# TPS2663.net
KiCad netlist of a schematic drawn in Altium Designer
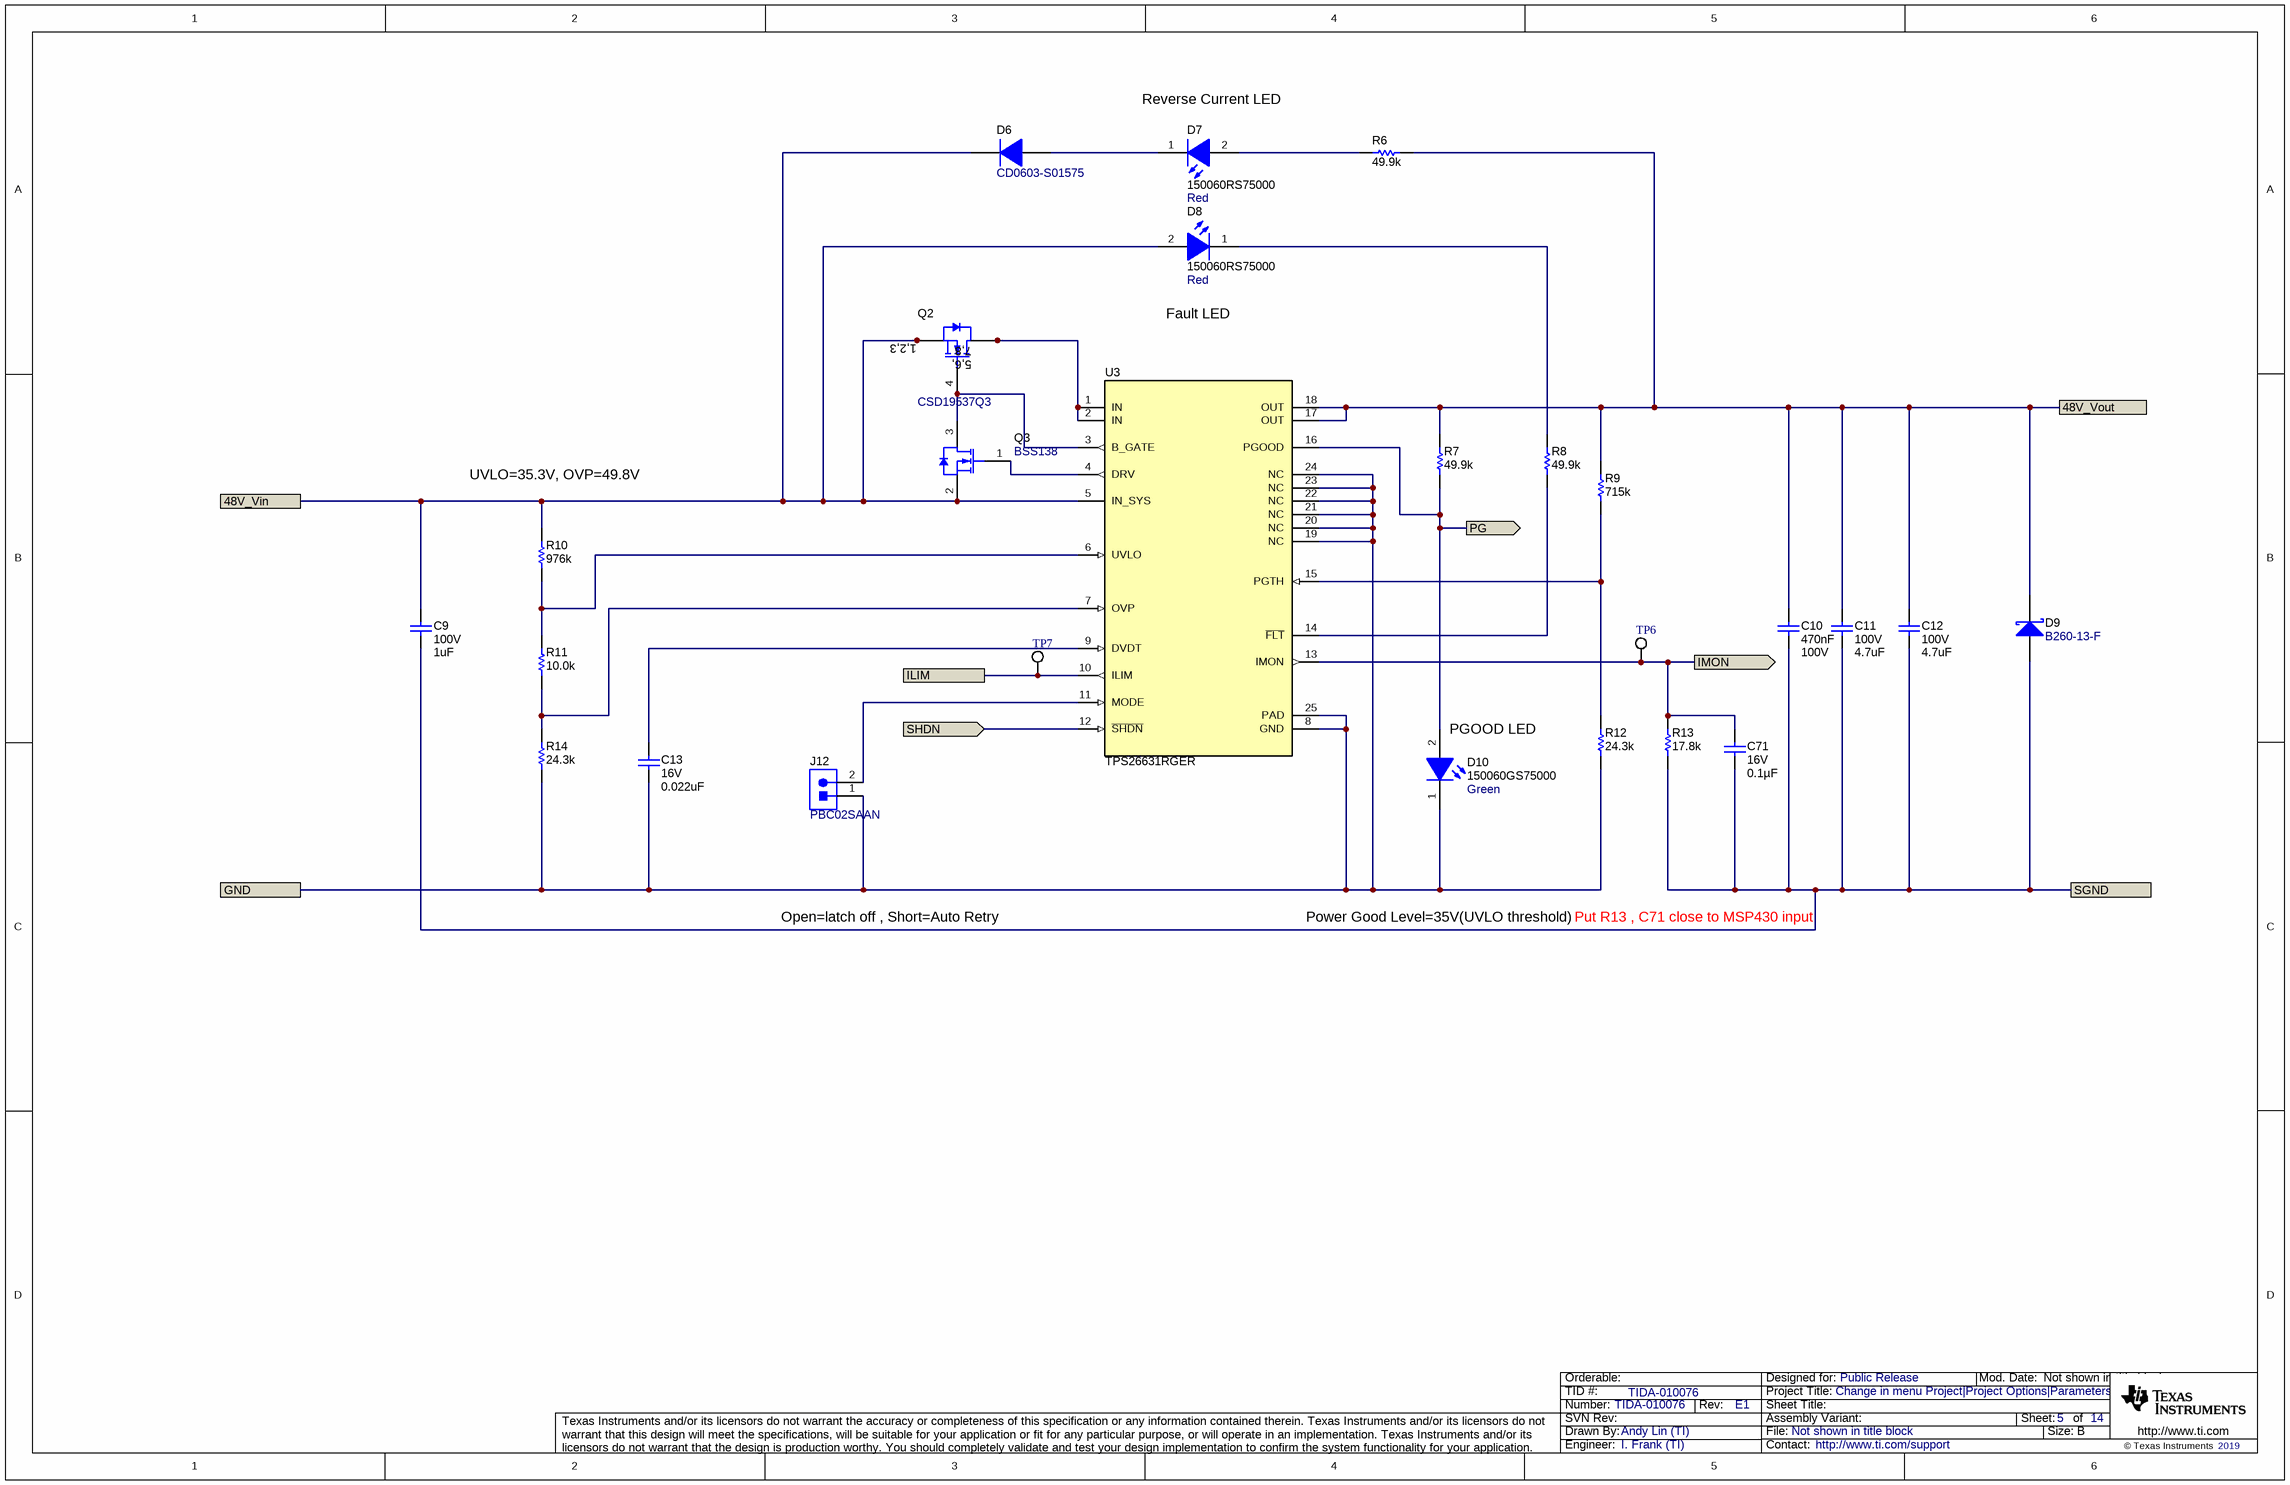
[diagram p0: TPS2663.SchDoc]

(export (version "E")
  (design (tool "Eeschema 10.0.6"))
  (components
    (comp (ref "C9")
      (value "GRM31CR72A105KA01L")
      (footprint "1206_180")
      (description "CAP, CERM, 1 uF, 100 V, +/- 10%, X7R, 1206")
      (fields
        (field (name "MANUFACTURER") "MuRata")
        (field (name "VDC_V") "100V")
        (field (name "VALUEDISPLAYED") "1uF")
        (field (name "PUBLISHER") "Texas Instruments")
      )
      (libsource (lib "Altium Vault - TI") (part "Capacitor"))
    )
    (comp (ref "C10")
      (value "GRM21BR72A474KA73L")
      (footprint "0805_HV")
      (description "CAP, CERM, 0.47 uF, 100 V, +/- 10%, X7R, 0805")
      (fields
        (field (name "MANUFACTURER") "MuRata")
        (field (name "CAP_F") "470nF")
        (field (name "VDC_V") "100V")
        (field (name "PUBLISHER") "Texas Instruments")
      )
      (libsource (lib "Altium Vault - TI") (part "Capacitor"))
    )
    (comp (ref "C11")
      (value "GRM32DC72A475KE01L")
      (footprint "1210_220")
      (description "CAP, CERM, 4.7 uF, 100 V, +/- 10%, X7S, 1210")
      (fields
        (field (name "MANUFACTURER") "MuRata")
        (field (name "VDC_V") "100V")
        (field (name "VALUEDISPLAYED") "4.7uF")
        (field (name "PUBLISHER") "Texas Instruments")
      )
      (libsource (lib "Altium Vault - TI") (part "Capacitor"))
    )
    (comp (ref "C12")
      (value "GRM32DC72A475KE01L")
      (footprint "1210_220")
      (description "CAP, CERM, 4.7 uF, 100 V, +/- 10%, X7S, 1210")
      (fields
        (field (name "MANUFACTURER") "MuRata")
        (field (name "VDC_V") "100V")
        (field (name "VALUEDISPLAYED") "4.7uF")
        (field (name "PUBLISHER") "Texas Instruments")
      )
      (libsource (lib "Altium Vault - TI") (part "Capacitor"))
    )
    (comp (ref "C13")
      (value "GRM155R71C223KA01D")
      (footprint "0402")
      (description "CAP, CERM, 0.022 uF, 16 V, +/- 10%, X7R, 0402")
      (fields
        (field (name "MANUFACTURER") "MuRata")
        (field (name "VDC_V") "16V")
        (field (name "VALUEDISPLAYED") "0.022uF")
        (field (name "PUBLISHER") "Texas Instruments")
      )
      (libsource (lib "Altium Vault - TI") (part "Capacitor"))
    )
    (comp (ref "C71")
      (value "GCM155R71C104JA55D")
      (footprint "0402")
      (description "CAP, CERM, 0.1 µF, 16 V,+/- 5%, X7R, AEC-Q200 Grade 1, 0402")
      (fields
        (field (name "MANUFACTURER") "MuRata")
        (field (name "VDC_V") "16V")
        (field (name "VALUEDISPLAYED") "0.1µF")
      )
      (libsource (lib "Altium Vault - TI") (part "Capacitor"))
    )
    (comp (ref "D6")
      (value "CD0603-S01575")
      (footprint "Diode_0603")
      (description "Diode, Switching, 100 V, 0.15 A, 0603 Diode")
      (fields (field (name "MANUFACTURER") "Bourns"))
      (libsource (lib "Altium Vault - TI") (part "DIODE"))
    )
    (comp (ref "D7")
      (value "150060RS75000")
      (footprint "WL-SMCW_RED")
      (description "LED, Red, SMD")
      (fields (field (name "ALTIUM_VALUE") "Red") (field (name "MANUFACTURER") "Wurth Elektronik"))
      (libsource (lib "Altium Vault - TI") (part "LED_A2_K1"))
    )
    (comp (ref "D8")
      (value "150060RS75000")
      (footprint "WL-SMCW_RED")
      (description "LED, Red, SMD")
      (fields (field (name "ALTIUM_VALUE") "Red") (field (name "MANUFACTURER") "Wurth Elektronik"))
      (libsource (lib "Altium Vault - TI") (part "LED_A2_K1"))
    )
    (comp (ref "D9")
      (value "B260-13-F")
      (footprint "SMB")
      (description "Diode, Schottky, 60 V, 2 A, SMB")
      (fields (field (name "MANUFACTURER") "Diodes Inc."))
      (libsource (lib "Altium Vault - TI") (part "DIODE_SCHOTTKY"))
    )
    (comp (ref "D10")
      (value "150060GS75000")
      (footprint "WL-SMCW_GREEN")
      (description "LED, Green, SMD")
      (fields (field (name "ALTIUM_VALUE") "Green") (field (name "MANUFACTURER") "Wurth Elektronik"))
      (libsource (lib "Altium Vault - TI") (part "LED_A2_K1"))
    )
    (comp (ref "J12")
      (value "PBC02SAAN")
      (footprint "Sullins_PBC02SAAN")
      (description "Header, 100mil, 2x1, Gold, TH")
      (fields
        (field (name "MANUFACTURER") "Sullins Connector Solutions")
        (field (name "PUBLISHER") "Texas Instruments")
      )
      (libsource (lib "Altium Vault - TI") (part "Header_2x1"))
    )
    (comp (ref "Q2")
      (value "CSD19537Q3")
      (footprint "DQG0008A")
      (description "MOSFET, N-CH, 100 V, 50 A, DQG0008A (VSON-CLIP-8)")
      (fields
        (field (name "MANUFACTURER") "Texas Instruments")
        (field (name "PUBLISHER") "Texas Instruments")
      )
      (libsource (lib "Altium Vault - TI") (part "MOSFET_N_D56789G4S123"))
    )
    (comp (ref "Q3")
      (value "BSS138")
      (footprint "SOT-23")
      (description "MOSFET, N-CH, 50 V, 0.22 A, SOT-23")
      (fields
        (field (name "MANUFACTURER") "Fairchild Semiconductor")
        (field (name "PUBLISHER") "Texas Instruments")
      )
      (libsource (lib "Altium Vault - TI") (part "MOSFET_N_D3G1S2"))
    )
    (comp (ref "R6")
      (value "CRCW060349K9FKEA")
      (footprint "0603")
      (description "RES, 49.9 k, 1%, 0.1 W, 0603")
      (fields
        (field (name "MANUFACTURER") "Vishay-Dale")
        (field (name "VALUEDISPLAYED") "49.9k")
        (field (name "PUBLISHER") "Texas Instruments")
      )
      (libsource (lib "Altium Vault - TI") (part "Resistor"))
    )
    (comp (ref "R7")
      (value "CRCW060349K9FKEA")
      (footprint "0603")
      (description "RES, 49.9 k, 1%, 0.1 W, 0603")
      (fields
        (field (name "MANUFACTURER") "Vishay-Dale")
        (field (name "VALUEDISPLAYED") "49.9k")
        (field (name "PUBLISHER") "Texas Instruments")
      )
      (libsource (lib "Altium Vault - TI") (part "Resistor"))
    )
    (comp (ref "R8")
      (value "CRCW060349K9FKEA")
      (footprint "0603")
      (description "RES, 49.9 k, 1%, 0.1 W, 0603")
      (fields
        (field (name "MANUFACTURER") "Vishay-Dale")
        (field (name "VALUEDISPLAYED") "49.9k")
        (field (name "PUBLISHER") "Texas Instruments")
      )
      (libsource (lib "Altium Vault - TI") (part "Resistor"))
    )
    (comp (ref "R9")
      (value "CRCW0402715KFKED")
      (footprint "0402")
      (description "RES, 715 k, 1%, 0.063 W, AEC-Q200 Grade 0, 0402")
      (fields (field (name "MANUFACTURER") "Vishay-Dale") (field (name "VALUEDISPLAYED") "715k"))
      (libsource (lib "Altium Vault - TI") (part "Resistor"))
    )
    (comp (ref "R10")
      (value "CRCW0402976KFKED")
      (footprint "0402")
      (description "RES, 976 k, 1%, 0.063 W, AEC-Q200 Grade 0, 0402")
      (fields (field (name "MANUFACTURER") "Vishay-Dale") (field (name "VALUEDISPLAYED") "976k"))
      (libsource (lib "Altium Vault - TI") (part "Resistor"))
    )
    (comp (ref "R11")
      (value "CRCW040210K0FKED")
      (footprint "0402")
      (description "RES, 10.0 k, 1%, 0.063 W, AEC-Q200 Grade 0, 0402")
      (fields (field (name "MANUFACTURER") "Vishay-Dale") (field (name "VALUEDISPLAYED") "10.0k"))
      (libsource (lib "Altium Vault - TI") (part "Resistor"))
    )
    (comp (ref "R12")
      (value "CRCW040224K3FKED")
      (footprint "0402")
      (description "RES, 24.3 k, 1%, 0.063 W, AEC-Q200 Grade 0, 0402")
      (fields (field (name "MANUFACTURER") "Vishay-Dale") (field (name "VALUEDISPLAYED") "24.3k"))
      (libsource (lib "Altium Vault - TI") (part "Resistor"))
    )
    (comp (ref "R13")
      (value "CRCW040217K8FKED")
      (footprint "0402")
      (description "RES, 17.8 k, 1%, 0.063 W, AEC-Q200 Grade 0, 0402")
      (fields (field (name "MANUFACTURER") "Vishay-Dale") (field (name "VALUEDISPLAYED") "17.8k"))
      (libsource (lib "Altium Vault - TI") (part "Resistor"))
    )
    (comp (ref "R14")
      (value "CRCW040224K3FKED")
      (footprint "0402")
      (description "RES, 24.3 k, 1%, 0.063 W, AEC-Q200 Grade 0, 0402")
      (fields (field (name "MANUFACTURER") "Vishay-Dale") (field (name "VALUEDISPLAYED") "24.3k"))
      (libsource (lib "Altium Vault - TI") (part "Resistor"))
    )
    (comp (ref "TP6")
      (value "5002")
      (footprint "Keystone5002")
      (description "Test Point, Miniature, White, TH")
      (fields (field (name "MANUFACTURER") "Keystone") (field (name "PUBLISHER") "Texas Instruments"))
      (libsource (lib "Altium Vault - TI") (part "5002"))
    )
    (comp (ref "TP7")
      (value "5002")
      (footprint "Keystone5002")
      (description "Test Point, Miniature, White, TH")
      (fields (field (name "MANUFACTURER") "Keystone") (field (name "PUBLISHER") "Texas Instruments"))
      (libsource (lib "Altium Vault - TI") (part "5002"))
    )
    (comp (ref "U3")
      (value "TPS26631RGER")
      (footprint "RGE0024H")
      (description "4.5V - 60V, 6A 29mΩ eFuse with Reverse Polarity Protection, RGE0024H (VQFN-24)")
      (fields
        (field (name "PARTNUMBER") "TPS26631RGER")
        (field (name "ALTERNATE PARTNUMBER") "TPS26631RGET")
        (field (name "MANUFACTURER") "Texas Instruments")
      )
      (libsource (lib "Altium Vault - TI") (part "TPS26630_1"))
    )
  )
  (nets
    (net (code "1") (name "/48V_Vin") (class "Default")
      (node (ref "C9") (pin "1") (pinfunction "1_1") (pintype "passive"))
      (node (ref "D6") (pin "1") (pinfunction "K_1") (pintype "passive"))
      (node (ref "D8") (pin "2") (pinfunction "A_2") (pintype "passive"))
      (node (ref "Q2") (pin "1") (pinfunction "S_1") (pintype "passive"))
      (node (ref "Q2") (pin "2") (pinfunction "S_2") (pintype "passive"))
      (node (ref "Q2") (pin "3") (pinfunction "S_3") (pintype "passive"))
      (node (ref "Q3") (pin "2") (pinfunction "S_2") (pintype "passive"))
      (node (ref "R10") (pin "2") (pinfunction "2_2") (pintype "passive"))
      (node (ref "U3") (pin "5") (pinfunction "IN_SYS_5") (pintype "power_in"))
    )
    (net (code "2") (name "/48V_Vout") (class "Default")
      (node (ref "C10") (pin "1") (pinfunction "1_1") (pintype "passive"))
      (node (ref "C11") (pin "1") (pinfunction "1_1") (pintype "passive"))
      (node (ref "C12") (pin "1") (pinfunction "1_1") (pintype "passive"))
      (node (ref "D9") (pin "1") (pinfunction "K_1") (pintype "passive"))
      (node (ref "R6") (pin "1") (pinfunction "1_1") (pintype "passive"))
      (node (ref "R7") (pin "2") (pinfunction "2_2") (pintype "passive"))
      (node (ref "R9") (pin "2") (pinfunction "2_2") (pintype "passive"))
      (node (ref "U3") (pin "17") (pinfunction "OUT_17") (pintype "power_in"))
      (node (ref "U3") (pin "18") (pinfunction "OUT_18") (pintype "power_in"))
    )
    (net (code "3") (name "/GND") (class "Default")
      (node (ref "C13") (pin "2") (pinfunction "2_2") (pintype "passive"))
      (node (ref "D10") (pin "1") (pinfunction "K_1") (pintype "passive"))
      (node (ref "J12") (pin "1") (pinfunction "1_1") (pintype "passive"))
      (node (ref "R12") (pin "1") (pinfunction "1_1") (pintype "passive"))
      (node (ref "R14") (pin "1") (pinfunction "1_1") (pintype "passive"))
      (node (ref "U3") (pin "19") (pinfunction "NC_19") (pintype "passive"))
      (node (ref "U3") (pin "20") (pinfunction "NC_20") (pintype "passive"))
      (node (ref "U3") (pin "21") (pinfunction "NC_21") (pintype "passive"))
      (node (ref "U3") (pin "22") (pinfunction "NC_22") (pintype "passive"))
      (node (ref "U3") (pin "23") (pinfunction "NC_23") (pintype "passive"))
      (node (ref "U3") (pin "24") (pinfunction "NC_24") (pintype "passive"))
      (node (ref "U3") (pin "25") (pinfunction "PAD_25") (pintype "power_in"))
      (node (ref "U3") (pin "8") (pinfunction "GND_8") (pintype "power_in"))
    )
    (net (code "4") (name "/ILIM") (class "Default")
      (node (ref "TP7") (pin "1") (pintype "passive"))
      (node (ref "U3") (pin "10") (pinfunction "ILIM_10") (pintype "output"))
    )
    (net (code "5") (name "/IMON") (class "Default")
      (node (ref "C71") (pin "1") (pinfunction "1_1") (pintype "passive"))
      (node (ref "R13") (pin "2") (pinfunction "2_2") (pintype "passive"))
      (node (ref "TP6") (pin "1") (pintype "passive"))
      (node (ref "U3") (pin "13") (pinfunction "IMON_13") (pintype "output"))
    )
    (net (code "6") (name "/PG") (class "Default")
      (node (ref "D10") (pin "2") (pinfunction "A_2") (pintype "passive"))
      (node (ref "R7") (pin "1") (pinfunction "1_1") (pintype "passive"))
      (node (ref "U3") (pin "16") (pinfunction "PGOOD_16") (pintype "open_collector"))
    )
    (net (code "7") (name "/SGND") (class "Default")
      (node (ref "C10") (pin "2") (pinfunction "2_2") (pintype "passive"))
      (node (ref "C11") (pin "2") (pinfunction "2_2") (pintype "passive"))
      (node (ref "C12") (pin "2") (pinfunction "2_2") (pintype "passive"))
      (node (ref "C71") (pin "2") (pinfunction "2_2") (pintype "passive"))
      (node (ref "C9") (pin "2") (pinfunction "2_2") (pintype "passive"))
      (node (ref "D9") (pin "2") (pinfunction "A_2") (pintype "passive"))
      (node (ref "R13") (pin "1") (pinfunction "1_1") (pintype "passive"))
    )
    (net (code "8") (name "/SHDN") (class "Default")
      (node (ref "U3") (pin "12") (pinfunction "~{SHDN}_12") (pintype "input"))
    )
    (net (code "9") (name "Net-(D6-A)") (class "Default")
      (node (ref "D6") (pin "2") (pinfunction "A_2") (pintype "passive"))
      (node (ref "D7") (pin "1") (pinfunction "K_1") (pintype "passive"))
    )
    (net (code "10") (name "Net-(D7-A)") (class "Default")
      (node (ref "D7") (pin "2") (pinfunction "A_2") (pintype "passive"))
      (node (ref "R6") (pin "2") (pinfunction "2_2") (pintype "passive"))
    )
    (net (code "11") (name "Net-(D8-K)") (class "Default")
      (node (ref "D8") (pin "1") (pinfunction "K_1") (pintype "passive"))
      (node (ref "R8") (pin "2") (pinfunction "2_2") (pintype "passive"))
    )
    (net (code "12") (name "Net-(Q2-D-Pad5)") (class "Default")
      (node (ref "Q2") (pin "5") (pinfunction "D_5") (pintype "passive"))
      (node (ref "Q2") (pin "6") (pinfunction "D_6") (pintype "passive"))
      (node (ref "Q2") (pin "7") (pinfunction "D_7") (pintype "passive"))
      (node (ref "Q2") (pin "8") (pinfunction "D_8") (pintype "passive"))
      (node (ref "Q2") (pin "9") (pinfunction "D_9") (pintype "passive"))
      (node (ref "U3") (pin "1") (pinfunction "IN_1") (pintype "power_in"))
      (node (ref "U3") (pin "2") (pinfunction "IN_2") (pintype "power_in"))
    )
    (net (code "13") (name "Net-(Q2-G)") (class "Default")
      (node (ref "Q2") (pin "4") (pinfunction "G_4") (pintype "passive"))
      (node (ref "Q3") (pin "3") (pinfunction "D_3") (pintype "passive"))
      (node (ref "U3") (pin "3") (pinfunction "B_GATE_3") (pintype "output"))
    )
    (net (code "14") (name "Net-(Q3-G)") (class "Default")
      (node (ref "Q3") (pin "1") (pinfunction "G_1") (pintype "passive"))
      (node (ref "U3") (pin "4") (pinfunction "DRV_4") (pintype "output"))
    )
    (net (code "15") (name "Net-(U3-DVDT)") (class "Default")
      (node (ref "C13") (pin "1") (pinfunction "1_1") (pintype "passive"))
      (node (ref "U3") (pin "9") (pinfunction "DVDT_9") (pintype "input"))
    )
    (net (code "16") (name "Net-(U3-MODE)") (class "Default")
      (node (ref "J12") (pin "2") (pinfunction "2_2") (pintype "passive"))
      (node (ref "U3") (pin "11") (pinfunction "MODE_11") (pintype "input"))
    )
    (net (code "17") (name "Net-(U3-OVP)") (class "Default")
      (node (ref "R11") (pin "1") (pinfunction "1_1") (pintype "passive"))
      (node (ref "R14") (pin "2") (pinfunction "2_2") (pintype "passive"))
      (node (ref "U3") (pin "7") (pinfunction "OVP_7") (pintype "input"))
    )
    (net (code "18") (name "Net-(U3-PGTH)") (class "Default")
      (node (ref "R12") (pin "2") (pinfunction "2_2") (pintype "passive"))
      (node (ref "R9") (pin "1") (pinfunction "1_1") (pintype "passive"))
      (node (ref "U3") (pin "15") (pinfunction "PGTH_15") (pintype "input"))
    )
    (net (code "19") (name "Net-(U3-UVLO)") (class "Default")
      (node (ref "R10") (pin "1") (pinfunction "1_1") (pintype "passive"))
      (node (ref "R11") (pin "2") (pinfunction "2_2") (pintype "passive"))
      (node (ref "U3") (pin "6") (pinfunction "UVLO_6") (pintype "input"))
    )
    (net (code "20") (name "Net-(U3-~{FLT})") (class "Default")
      (node (ref "R8") (pin "1") (pinfunction "1_1") (pintype "passive"))
      (node (ref "U3") (pin "14") (pinfunction "~{FLT}_14") (pintype "open_collector"))
    )
  )
)
